# Sheet2.net
KiCad netlist of a schematic drawn in Altium Designer
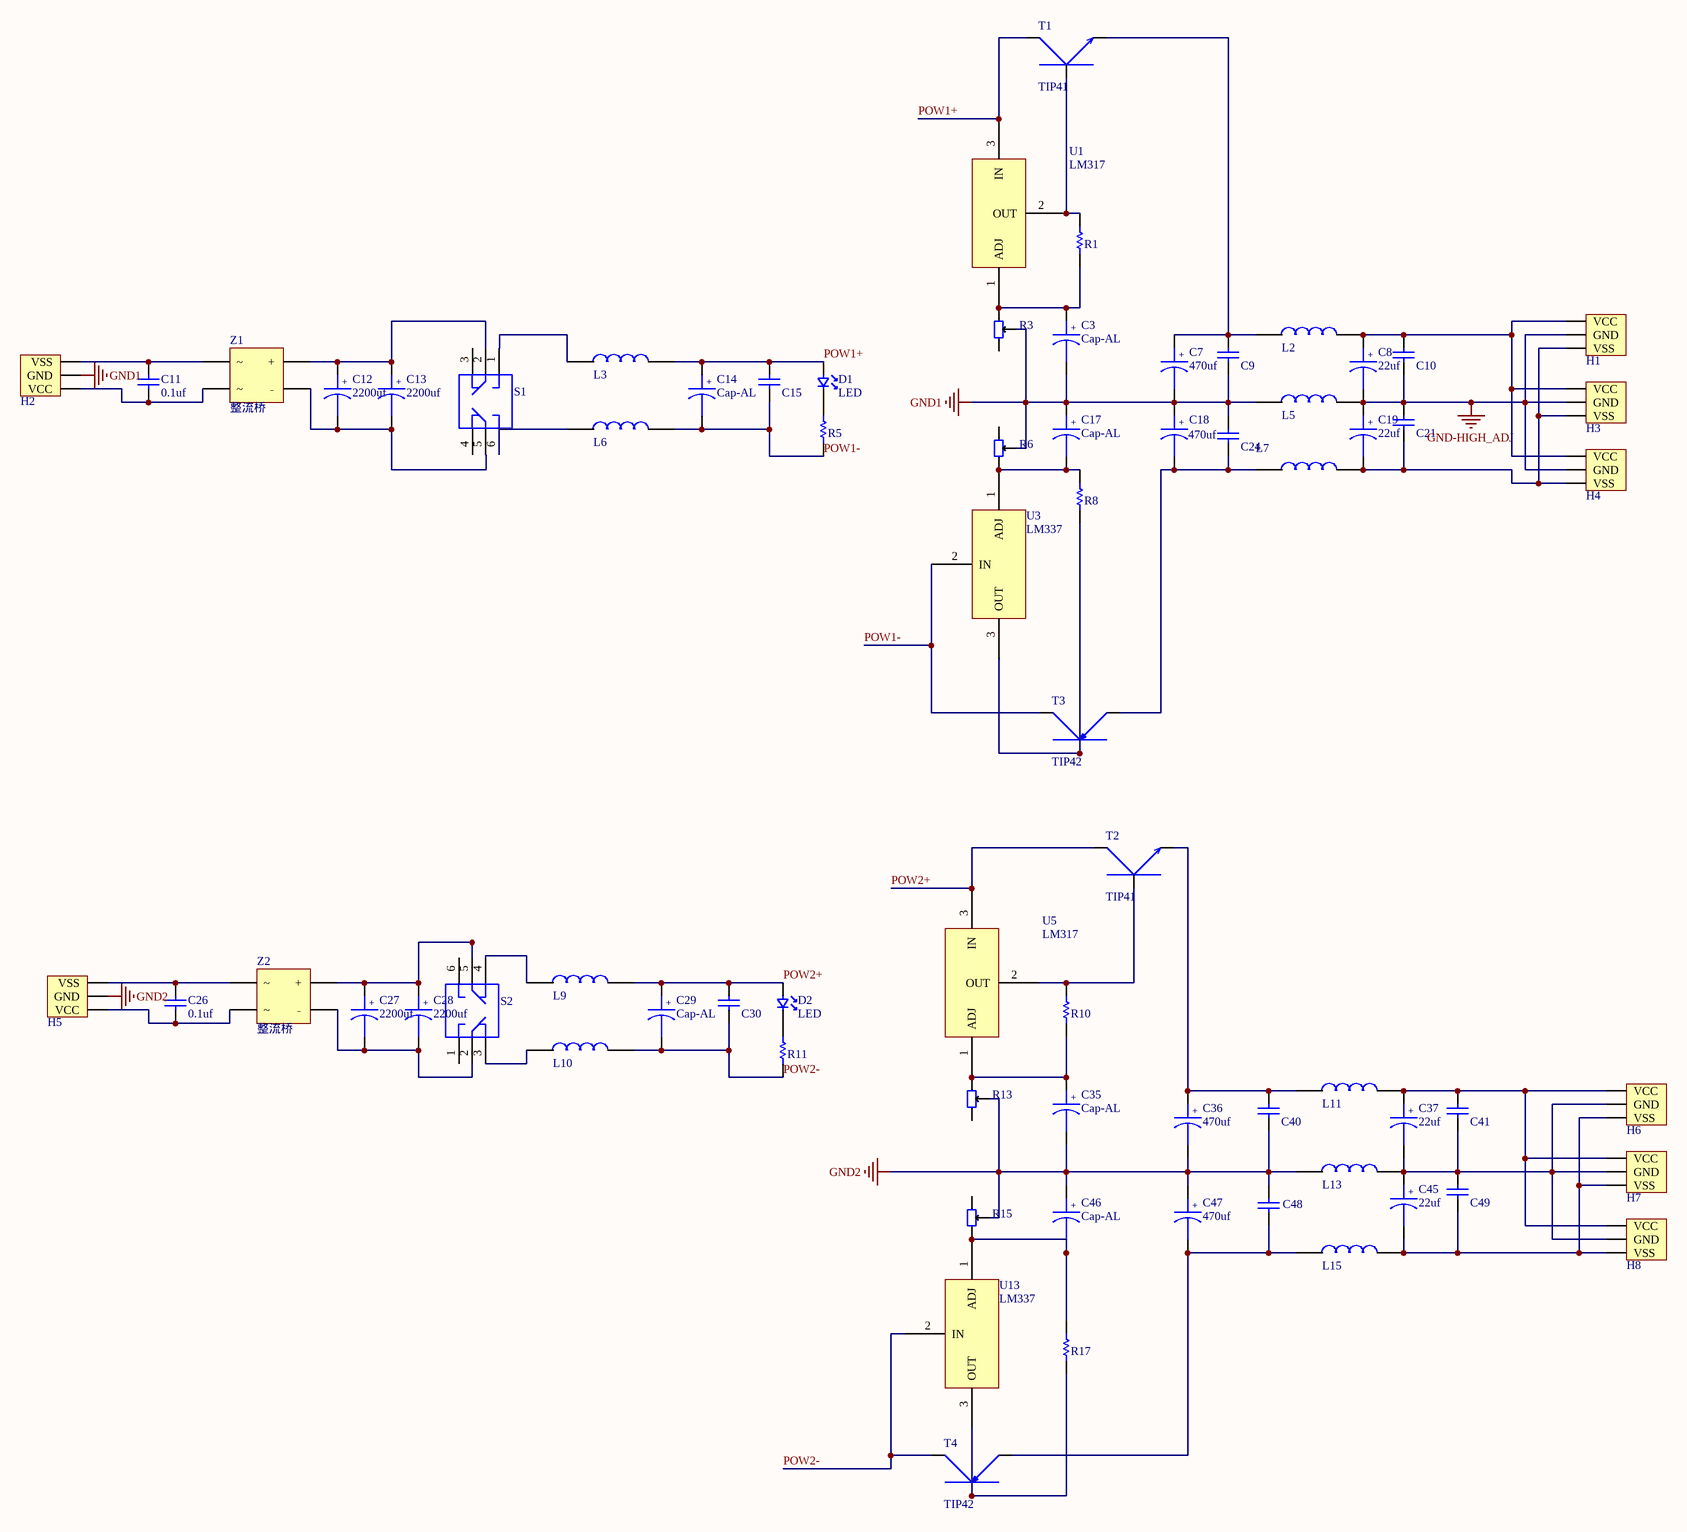
[diagram p0: Sheet2.SchDoc]

(export (version "E")
  (design (tool "Eeschema 10.0.6"))
  (components
    (comp (ref "C3") (value "Cap-AL") (footprint "CD-2.2mm") (libsource (lib "电源") (part "Cap-AL")))
    (comp (ref "C7") (value "470uf") (footprint "CD-5mm") (libsource (lib "电源") (part "Cap-AL")))
    (comp (ref "C8") (value "22uf") (footprint "CD-3mm") (libsource (lib "电源") (part "Cap-AL")))
    (comp (ref "C9") (value "Cap-SEMI") (footprint "独石电容") (libsource (lib "电源") (part "Cap-SEMI")))
    (comp (ref "C10") (value "Cap-SEMI") (footprint "独石电容") (libsource (lib "电源") (part "Cap-SEMI")))
    (comp (ref "C11")
      (value "Cap1")
      (footprint "安规电容")
      (fields (field (name "值") "0.1uf"))
      (libsource (lib "电源") (part "Cap1"))
    )
    (comp (ref "C12") (value "2200uf") (footprint "CD-7.6mm") (libsource (lib "电源") (part "Cap")))
    (comp (ref "C13") (value "2200uf") (footprint "CD-7.6mm") (libsource (lib "电源") (part "Cap")))
    (comp (ref "C14") (value "Cap-AL") (footprint "CD-3mm") (libsource (lib "电源") (part "Cap-AL")))
    (comp (ref "C15") (value "0.1uf") (footprint "独石电容") (libsource (lib "电源") (part "Cap-SEMI")))
    (comp (ref "C17") (value "Cap-AL") (footprint "CD-2.2mm") (libsource (lib "电源") (part "Cap-AL")))
    (comp (ref "C18") (value "470uf") (footprint "CD-5mm") (libsource (lib "电源") (part "Cap-AL")))
    (comp (ref "C19") (value "22uf") (footprint "CD-3mm") (libsource (lib "电源") (part "Cap-AL")))
    (comp (ref "C21") (value "Cap-SEMI") (footprint "独石电容") (libsource (lib "电源") (part "Cap-SEMI")))
    (comp (ref "C24") (value "Cap-SEMI") (footprint "独石电容") (libsource (lib "电源") (part "Cap-SEMI")))
    (comp (ref "C26")
      (value "Cap1")
      (footprint "安规电容")
      (fields (field (name "值") "0.1uf"))
      (libsource (lib "电源") (part "Cap1"))
    )
    (comp (ref "C27") (value "2200uf") (footprint "CD-7.6mm") (libsource (lib "电源") (part "Cap")))
    (comp (ref "C28") (value "2200uf") (footprint "CD-7.6mm") (libsource (lib "电源") (part "Cap")))
    (comp (ref "C29") (value "Cap-AL") (footprint "CD-3mm") (libsource (lib "电源") (part "Cap-AL")))
    (comp (ref "C30") (value "0.1uf") (footprint "独石电容") (libsource (lib "电源") (part "Cap-SEMI")))
    (comp (ref "C35") (value "Cap-AL") (footprint "CD-2.2mm") (libsource (lib "电源") (part "Cap-AL")))
    (comp (ref "C36") (value "470uf") (footprint "CD-5mm") (libsource (lib "电源") (part "Cap-AL")))
    (comp (ref "C37") (value "22uf") (footprint "CD-3mm") (libsource (lib "电源") (part "Cap-AL")))
    (comp (ref "C40") (value "Cap-SEMI") (footprint "独石电容") (libsource (lib "电源") (part "Cap-SEMI")))
    (comp (ref "C41") (value "Cap-SEMI") (footprint "独石电容") (libsource (lib "电源") (part "Cap-SEMI")))
    (comp (ref "C45") (value "22uf") (footprint "CD-3mm") (libsource (lib "电源") (part "Cap-AL")))
    (comp (ref "C46") (value "Cap-AL") (footprint "CD-2.2mm") (libsource (lib "电源") (part "Cap-AL")))
    (comp (ref "C47") (value "470uf") (footprint "CD-5mm") (libsource (lib "电源") (part "Cap-AL")))
    (comp (ref "C48") (value "Cap-SEMI") (footprint "独石电容") (libsource (lib "电源") (part "Cap-SEMI")))
    (comp (ref "C49") (value "Cap-SEMI") (footprint "独石电容") (libsource (lib "电源") (part "Cap-SEMI")))
    (comp (ref "D1") (value "LED") (footprint "0805_s") (libsource (lib "电源") (part "LED")))
    (comp (ref "D2") (value "LED") (footprint "0805_s") (libsource (lib "电源") (part "LED")))
    (comp (ref "H1")
      (value "KF128-5.08-3P")
      (footprint "KF128-5.08-3P")
      (libsource (lib "电源") (part "KF128-5.08-3P"))
    )
    (comp (ref "H2")
      (value "KF128-5.08-3P")
      (footprint "KF128-5.08-3P")
      (libsource (lib "") (part "KF128-5.08-3P_1"))
    )
    (comp (ref "H3")
      (value "KF128-5.08-3P")
      (footprint "KF128-5.08-3P")
      (libsource (lib "电源") (part "KF128-5.08-3P"))
    )
    (comp (ref "H4")
      (value "KF128-5.08-3P")
      (footprint "KF128-5.08-3P")
      (libsource (lib "电源") (part "KF128-5.08-3P"))
    )
    (comp (ref "H5")
      (value "KF128-5.08-3P")
      (footprint "KF128-5.08-3P")
      (libsource (lib "") (part "KF128-5.08-3P_1"))
    )
    (comp (ref "H6")
      (value "KF128-5.08-3P")
      (footprint "KF128-5.08-3P")
      (libsource (lib "电源") (part "KF128-5.08-3P"))
    )
    (comp (ref "H7")
      (value "KF128-5.08-3P")
      (footprint "KF128-5.08-3P")
      (libsource (lib "电源") (part "KF128-5.08-3P"))
    )
    (comp (ref "H8")
      (value "KF128-5.08-3P")
      (footprint "KF128-5.08-3P")
      (libsource (lib "电源") (part "KF128-5.08-3P"))
    )
    (comp (ref "L2") (value "SMD") (footprint "功率电感-12x12 - duplicate") (libsource (lib "电源") (part "功率电感")))
    (comp (ref "L3") (value "SMD") (footprint "功率电感-12x12 - duplicate") (libsource (lib "电源") (part "功率电感")))
    (comp (ref "L5") (value "SMD") (footprint "功率电感-12x12 - duplicate") (libsource (lib "电源") (part "功率电感")))
    (comp (ref "L6") (value "SMD") (footprint "功率电感-12x12 - duplicate") (libsource (lib "电源") (part "功率电感")))
    (comp (ref "L7") (value "SMD") (footprint "功率电感-12x12 - duplicate") (libsource (lib "电源") (part "功率电感")))
    (comp (ref "L9") (value "SMD") (footprint "功率电感-12x12 - duplicate") (libsource (lib "电源") (part "功率电感")))
    (comp (ref "L10") (value "SMD") (footprint "功率电感-12x12 - duplicate") (libsource (lib "电源") (part "功率电感")))
    (comp (ref "L11") (value "SMD") (footprint "功率电感-12x12 - duplicate") (libsource (lib "电源") (part "功率电感")))
    (comp (ref "L13") (value "SMD") (footprint "功率电感-12x12 - duplicate") (libsource (lib "电源") (part "功率电感")))
    (comp (ref "L15") (value "SMD") (footprint "功率电感-12x12 - duplicate") (libsource (lib "电源") (part "功率电感")))
    (comp (ref "R1") (value "RES") (footprint "0805") (libsource (lib "电源") (part "RES")))
    (comp (ref "R3") (value "可调电位器1") (footprint "电位器") (libsource (lib "电源") (part "可调电位器1")))
    (comp (ref "R5") (value "RES") (footprint "0805") (libsource (lib "电源") (part "RES")))
    (comp (ref "R6") (value "可调电位器1") (footprint "电位器") (libsource (lib "电源") (part "可调电位器1")))
    (comp (ref "R8") (value "RES") (footprint "0805") (libsource (lib "电源") (part "RES")))
    (comp (ref "R10") (value "RES") (footprint "0805") (libsource (lib "电源") (part "RES")))
    (comp (ref "R11") (value "RES") (footprint "0805") (libsource (lib "电源") (part "RES")))
    (comp (ref "R13") (value "可调电位器1") (footprint "电位器") (libsource (lib "电源") (part "可调电位器1")))
    (comp (ref "R15") (value "可调电位器1") (footprint "电位器") (libsource (lib "电源") (part "可调电位器1")))
    (comp (ref "R17") (value "RES") (footprint "0805") (libsource (lib "电源") (part "RES")))
    (comp (ref "S1") (value "双掷开关") (footprint "SWITCH") (libsource (lib "电源") (part "双掷开关")))
    (comp (ref "S2") (value "双掷开关") (footprint "SWITCH") (libsource (lib "电源") (part "双掷开关")))
    (comp (ref "T1") (value "TIP41") (footprint "TO-220") (libsource (lib "电源") (part "TIP41")))
    (comp (ref "T2") (value "TIP41") (footprint "TO-220") (libsource (lib "电源") (part "TIP41")))
    (comp (ref "T3") (value "TIP42") (footprint "TO-220") (libsource (lib "电源") (part "TIP42")))
    (comp (ref "T4") (value "TIP42") (footprint "TO-220") (libsource (lib "电源") (part "TIP42")))
    (comp (ref "U1") (value "LM317") (footprint "TO-220") (libsource (lib "电源") (part "LM317")))
    (comp (ref "U3") (value "LM337") (footprint "TO-220") (libsource (lib "电源") (part "LM337")))
    (comp (ref "U5") (value "LM317") (footprint "TO-220") (libsource (lib "电源") (part "LM317")))
    (comp (ref "U13") (value "LM337") (footprint "TO-220") (libsource (lib "电源") (part "LM337")))
    (comp (ref "Z1") (value "整流桥") (footprint "整流桥") (libsource (lib "电源") (part "整流桥")))
    (comp (ref "Z2") (value "整流桥") (footprint "整流桥") (libsource (lib "电源") (part "整流桥")))
  )
  (nets
    (net (code "1") (name "/POW1+") (class "Default")
      (node (ref "C14") (pin "1") (pinfunction "1_1") (pintype "passive"))
      (node (ref "C15") (pin "2") (pinfunction "2_2") (pintype "passive"))
      (node (ref "D1") (pin "2") (pinfunction "2_2") (pintype "passive"))
      (node (ref "L3") (pin "2") (pintype "passive"))
      (node (ref "T1") (pin "2") (pinfunction "2_2") (pintype "passive"))
      (node (ref "U1") (pin "3") (pinfunction "IN_3") (pintype "passive"))
    )
    (net (code "2") (name "/POW1-") (class "Default")
      (node (ref "C14") (pin "2") (pinfunction "2_2") (pintype "passive"))
      (node (ref "C15") (pin "1") (pinfunction "1_1") (pintype "passive"))
      (node (ref "L6") (pin "2") (pintype "passive"))
      (node (ref "R5") (pin "1") (pinfunction "1_1") (pintype "passive"))
      (node (ref "T3") (pin "2") (pinfunction "2_2") (pintype "passive"))
      (node (ref "U3") (pin "2") (pinfunction "IN_2") (pintype "passive"))
    )
    (net (code "3") (name "/POW2+") (class "Default")
      (node (ref "C29") (pin "1") (pinfunction "1_1") (pintype "passive"))
      (node (ref "C30") (pin "2") (pinfunction "2_2") (pintype "passive"))
      (node (ref "D2") (pin "2") (pinfunction "2_2") (pintype "passive"))
      (node (ref "L9") (pin "2") (pintype "passive"))
      (node (ref "T2") (pin "2") (pinfunction "2_2") (pintype "passive"))
      (node (ref "U5") (pin "3") (pinfunction "IN_3") (pintype "passive"))
    )
    (net (code "4") (name "/POW2-") (class "Default")
      (node (ref "C29") (pin "2") (pinfunction "2_2") (pintype "passive"))
      (node (ref "C30") (pin "1") (pinfunction "1_1") (pintype "passive"))
      (node (ref "L10") (pin "2") (pintype "passive"))
      (node (ref "R11") (pin "1") (pinfunction "1_1") (pintype "passive"))
      (node (ref "T4") (pin "2") (pinfunction "2_2") (pintype "passive"))
      (node (ref "U13") (pin "2") (pinfunction "IN_2") (pintype "passive"))
    )
    (net (code "5") (name "GND-HIGH_ADJ") (class "Default")
      (node (ref "C10") (pin "1") (pinfunction "1_1") (pintype "passive"))
      (node (ref "C19") (pin "1") (pinfunction "1_1") (pintype "passive"))
      (node (ref "C21") (pin "2") (pinfunction "2_2") (pintype "passive"))
      (node (ref "C8") (pin "2") (pinfunction "2_2") (pintype "passive"))
      (node (ref "H1") (pin "2") (pinfunction "GND_2") (pintype "passive"))
      (node (ref "H3") (pin "2") (pinfunction "GND_2") (pintype "passive"))
      (node (ref "H4") (pin "2") (pinfunction "GND_2") (pintype "passive"))
      (node (ref "L5") (pin "2") (pintype "passive"))
    )
    (net (code "6") (name "GND1") (class "Default")
      (node (ref "C17") (pin "1") (pinfunction "1_1") (pintype "passive"))
      (node (ref "C18") (pin "1") (pinfunction "1_1") (pintype "passive"))
      (node (ref "C24") (pin "2") (pinfunction "2_2") (pintype "passive"))
      (node (ref "C3") (pin "2") (pinfunction "2_2") (pintype "passive"))
      (node (ref "C7") (pin "2") (pinfunction "2_2") (pintype "passive"))
      (node (ref "C9") (pin "1") (pinfunction "1_1") (pintype "passive"))
      (node (ref "H2") (pin "2") (pinfunction "GND_2") (pintype "passive"))
      (node (ref "L5") (pin "1") (pintype "passive"))
      (node (ref "R3") (pin "2") (pinfunction "2_2") (pintype "passive"))
      (node (ref "R6") (pin "2") (pinfunction "2_2") (pintype "passive"))
    )
    (net (code "7") (name "GND2") (class "Default")
      (node (ref "C35") (pin "2") (pinfunction "2_2") (pintype "passive"))
      (node (ref "C36") (pin "2") (pinfunction "2_2") (pintype "passive"))
      (node (ref "C40") (pin "1") (pinfunction "1_1") (pintype "passive"))
      (node (ref "C46") (pin "1") (pinfunction "1_1") (pintype "passive"))
      (node (ref "C47") (pin "1") (pinfunction "1_1") (pintype "passive"))
      (node (ref "C48") (pin "2") (pinfunction "2_2") (pintype "passive"))
      (node (ref "H5") (pin "2") (pinfunction "GND_2") (pintype "passive"))
      (node (ref "L13") (pin "1") (pintype "passive"))
      (node (ref "R13") (pin "2") (pinfunction "2_2") (pintype "passive"))
      (node (ref "R15") (pin "2") (pinfunction "2_2") (pintype "passive"))
    )
    (net (code "8") (name "Net-(C7-Pad1)") (class "Default")
      (node (ref "C7") (pin "1") (pinfunction "1_1") (pintype "passive"))
      (node (ref "C9") (pin "2") (pinfunction "2_2") (pintype "passive"))
      (node (ref "L2") (pin "1") (pintype "passive"))
      (node (ref "T1") (pin "3") (pinfunction "3_3") (pintype "passive"))
    )
    (net (code "9") (name "Net-(C18-Pad2)") (class "Default")
      (node (ref "C18") (pin "2") (pinfunction "2_2") (pintype "passive"))
      (node (ref "C24") (pin "1") (pinfunction "1_1") (pintype "passive"))
      (node (ref "L7") (pin "1") (pintype "passive"))
      (node (ref "T3") (pin "3") (pinfunction "3_3") (pintype "passive"))
    )
    (net (code "10") (name "Net-(C36-Pad1)") (class "Default")
      (node (ref "C36") (pin "1") (pinfunction "1_1") (pintype "passive"))
      (node (ref "C40") (pin "2") (pinfunction "2_2") (pintype "passive"))
      (node (ref "L11") (pin "1") (pintype "passive"))
      (node (ref "T2") (pin "3") (pinfunction "3_3") (pintype "passive"))
    )
    (net (code "11") (name "Net-(C47-Pad2)") (class "Default")
      (node (ref "C47") (pin "2") (pinfunction "2_2") (pintype "passive"))
      (node (ref "C48") (pin "1") (pinfunction "1_1") (pintype "passive"))
      (node (ref "L15") (pin "1") (pintype "passive"))
      (node (ref "T4") (pin "3") (pinfunction "3_3") (pintype "passive"))
    )
    (net (code "12") (name "Net-(D1-Pad1)") (class "Default")
      (node (ref "D1") (pin "1") (pinfunction "1_1") (pintype "passive"))
      (node (ref "R5") (pin "2") (pinfunction "2_2") (pintype "passive"))
    )
    (net (code "13") (name "Net-(D2-Pad1)") (class "Default")
      (node (ref "D2") (pin "1") (pinfunction "1_1") (pintype "passive"))
      (node (ref "R11") (pin "2") (pinfunction "2_2") (pintype "passive"))
    )
    (net (code "14") (name "Net-(H1-VCC)") (class "Default")
      (node (ref "C10") (pin "2") (pinfunction "2_2") (pintype "passive"))
      (node (ref "C8") (pin "1") (pinfunction "1_1") (pintype "passive"))
      (node (ref "H1") (pin "1") (pinfunction "VCC_1") (pintype "passive"))
      (node (ref "H3") (pin "1") (pinfunction "VCC_1") (pintype "passive"))
      (node (ref "H4") (pin "1") (pinfunction "VCC_1") (pintype "passive"))
      (node (ref "L2") (pin "2") (pintype "passive"))
    )
    (net (code "15") (name "Net-(H1-VSS)") (class "Default")
      (node (ref "C19") (pin "2") (pinfunction "2_2") (pintype "passive"))
      (node (ref "C21") (pin "1") (pinfunction "1_1") (pintype "passive"))
      (node (ref "H1") (pin "3") (pinfunction "VSS_3") (pintype "passive"))
      (node (ref "H3") (pin "3") (pinfunction "VSS_3") (pintype "passive"))
      (node (ref "H4") (pin "3") (pinfunction "VSS_3") (pintype "passive"))
      (node (ref "L7") (pin "2") (pintype "passive"))
    )
    (net (code "16") (name "Net-(H2-VCC)") (class "Default")
      (node (ref "C11") (pin "1") (pinfunction "1_1") (pintype "passive"))
      (node (ref "H2") (pin "1") (pinfunction "VCC_1") (pintype "passive"))
      (node (ref "Z1") (pin "3") (pinfunction "~_3") (pintype "passive"))
    )
    (net (code "17") (name "Net-(H2-VSS)") (class "Default")
      (node (ref "C11") (pin "2") (pinfunction "2_2") (pintype "passive"))
      (node (ref "H2") (pin "3") (pinfunction "VSS_3") (pintype "passive"))
      (node (ref "Z1") (pin "2") (pinfunction "~_2") (pintype "passive"))
    )
    (net (code "18") (name "Net-(H5-VCC)") (class "Default")
      (node (ref "C26") (pin "1") (pinfunction "1_1") (pintype "passive"))
      (node (ref "H5") (pin "1") (pinfunction "VCC_1") (pintype "passive"))
      (node (ref "Z2") (pin "3") (pinfunction "~_3") (pintype "passive"))
    )
    (net (code "19") (name "Net-(H5-VSS)") (class "Default")
      (node (ref "C26") (pin "2") (pinfunction "2_2") (pintype "passive"))
      (node (ref "H5") (pin "3") (pinfunction "VSS_3") (pintype "passive"))
      (node (ref "Z2") (pin "2") (pinfunction "~_2") (pintype "passive"))
    )
    (net (code "20") (name "Net-(H6-GND)") (class "Default")
      (node (ref "C37") (pin "2") (pinfunction "2_2") (pintype "passive"))
      (node (ref "C41") (pin "1") (pinfunction "1_1") (pintype "passive"))
      (node (ref "C45") (pin "1") (pinfunction "1_1") (pintype "passive"))
      (node (ref "C49") (pin "2") (pinfunction "2_2") (pintype "passive"))
      (node (ref "H6") (pin "2") (pinfunction "GND_2") (pintype "passive"))
      (node (ref "H7") (pin "2") (pinfunction "GND_2") (pintype "passive"))
      (node (ref "H8") (pin "2") (pinfunction "GND_2") (pintype "passive"))
      (node (ref "L13") (pin "2") (pintype "passive"))
    )
    (net (code "21") (name "Net-(H6-VCC)") (class "Default")
      (node (ref "C37") (pin "1") (pinfunction "1_1") (pintype "passive"))
      (node (ref "C41") (pin "2") (pinfunction "2_2") (pintype "passive"))
      (node (ref "H6") (pin "1") (pinfunction "VCC_1") (pintype "passive"))
      (node (ref "H7") (pin "1") (pinfunction "VCC_1") (pintype "passive"))
      (node (ref "H8") (pin "1") (pinfunction "VCC_1") (pintype "passive"))
      (node (ref "L11") (pin "2") (pintype "passive"))
    )
    (net (code "22") (name "Net-(H6-VSS)") (class "Default")
      (node (ref "C45") (pin "2") (pinfunction "2_2") (pintype "passive"))
      (node (ref "C49") (pin "1") (pinfunction "1_1") (pintype "passive"))
      (node (ref "H6") (pin "3") (pinfunction "VSS_3") (pintype "passive"))
      (node (ref "H7") (pin "3") (pinfunction "VSS_3") (pintype "passive"))
      (node (ref "H8") (pin "3") (pinfunction "VSS_3") (pintype "passive"))
      (node (ref "L15") (pin "2") (pintype "passive"))
    )
    (net (code "23") (name "Net-(L3-Pad1)") (class "Default")
      (node (ref "L3") (pin "1") (pintype "passive"))
      (node (ref "S1") (pin "1") (pinfunction "1_1") (pintype "passive"))
    )
    (net (code "24") (name "Net-(L6-Pad1)") (class "Default")
      (node (ref "L6") (pin "1") (pintype "passive"))
      (node (ref "S1") (pin "6") (pinfunction "6_6") (pintype "passive"))
    )
    (net (code "25") (name "Net-(L9-Pad1)") (class "Default")
      (node (ref "L9") (pin "1") (pintype "passive"))
      (node (ref "S2") (pin "4") (pinfunction "4_4") (pintype "passive"))
    )
    (net (code "26") (name "Net-(L10-Pad1)") (class "Default")
      (node (ref "L10") (pin "1") (pintype "passive"))
      (node (ref "S2") (pin "3") (pinfunction "3_3") (pintype "passive"))
    )
    (net (code "27") (name "Net-(U1-ADJ)") (class "Default")
      (node (ref "C3") (pin "1") (pinfunction "1_1") (pintype "passive"))
      (node (ref "R1") (pin "1") (pinfunction "1_1") (pintype "passive"))
      (node (ref "R3") (pin "3") (pinfunction "3_3") (pintype "passive"))
      (node (ref "U1") (pin "1") (pinfunction "ADJ_1") (pintype "passive"))
    )
    (net (code "28") (name "Net-(U1-OUT)") (class "Default")
      (node (ref "R1") (pin "2") (pinfunction "2_2") (pintype "passive"))
      (node (ref "T1") (pin "1") (pinfunction "1_1") (pintype "passive"))
      (node (ref "U1") (pin "2") (pinfunction "OUT_2") (pintype "passive"))
    )
    (net (code "29") (name "Net-(U3-ADJ)") (class "Default")
      (node (ref "C17") (pin "2") (pinfunction "2_2") (pintype "passive"))
      (node (ref "R6") (pin "1") (pinfunction "1_1") (pintype "passive"))
      (node (ref "R8") (pin "2") (pinfunction "2_2") (pintype "passive"))
      (node (ref "U3") (pin "1") (pinfunction "ADJ_1") (pintype "passive"))
    )
    (net (code "30") (name "Net-(U3-OUT)") (class "Default")
      (node (ref "R8") (pin "1") (pinfunction "1_1") (pintype "passive"))
      (node (ref "T3") (pin "1") (pinfunction "1_1") (pintype "passive"))
      (node (ref "U3") (pin "3") (pinfunction "OUT_3") (pintype "passive"))
    )
    (net (code "31") (name "Net-(U5-ADJ)") (class "Default")
      (node (ref "C35") (pin "1") (pinfunction "1_1") (pintype "passive"))
      (node (ref "R10") (pin "1") (pinfunction "1_1") (pintype "passive"))
      (node (ref "R13") (pin "3") (pinfunction "3_3") (pintype "passive"))
      (node (ref "U5") (pin "1") (pinfunction "ADJ_1") (pintype "passive"))
    )
    (net (code "32") (name "Net-(U5-OUT)") (class "Default")
      (node (ref "R10") (pin "2") (pinfunction "2_2") (pintype "passive"))
      (node (ref "T2") (pin "1") (pinfunction "1_1") (pintype "passive"))
      (node (ref "U5") (pin "2") (pinfunction "OUT_2") (pintype "passive"))
    )
    (net (code "33") (name "Net-(U13-ADJ)") (class "Default")
      (node (ref "C46") (pin "2") (pinfunction "2_2") (pintype "passive"))
      (node (ref "R15") (pin "1") (pinfunction "1_1") (pintype "passive"))
      (node (ref "R17") (pin "2") (pinfunction "2_2") (pintype "passive"))
      (node (ref "U13") (pin "1") (pinfunction "ADJ_1") (pintype "passive"))
    )
    (net (code "34") (name "Net-(U13-OUT)") (class "Default")
      (node (ref "R17") (pin "1") (pinfunction "1_1") (pintype "passive"))
      (node (ref "T4") (pin "1") (pinfunction "1_1") (pintype "passive"))
      (node (ref "U13") (pin "3") (pinfunction "OUT_3") (pintype "passive"))
    )
    (net (code "35") (name "Net-(Z1-+)") (class "Default")
      (node (ref "C12") (pin "1") (pinfunction "1_1") (pintype "passive"))
      (node (ref "C13") (pin "1") (pinfunction "1_1") (pintype "passive"))
      (node (ref "S1") (pin "2") (pinfunction "2_2") (pintype "passive"))
      (node (ref "Z1") (pin "1") (pinfunction "+_1") (pintype "passive"))
    )
    (net (code "36") (name "Net-(Z1-﹣)") (class "Default")
      (node (ref "C12") (pin "2") (pinfunction "2_2") (pintype "passive"))
      (node (ref "C13") (pin "2") (pinfunction "2_2") (pintype "passive"))
      (node (ref "S1") (pin "5") (pinfunction "5_5") (pintype "passive"))
      (node (ref "Z1") (pin "4") (pinfunction "﹣_4") (pintype "passive"))
    )
    (net (code "37") (name "Net-(Z2-+)") (class "Default")
      (node (ref "C27") (pin "1") (pinfunction "1_1") (pintype "passive"))
      (node (ref "C28") (pin "1") (pinfunction "1_1") (pintype "passive"))
      (node (ref "S2") (pin "5") (pinfunction "5_5") (pintype "passive"))
      (node (ref "Z2") (pin "1") (pinfunction "+_1") (pintype "passive"))
    )
    (net (code "38") (name "Net-(Z2-﹣)") (class "Default")
      (node (ref "C27") (pin "2") (pinfunction "2_2") (pintype "passive"))
      (node (ref "C28") (pin "2") (pinfunction "2_2") (pintype "passive"))
      (node (ref "S2") (pin "2") (pinfunction "2_2") (pintype "passive"))
      (node (ref "Z2") (pin "4") (pinfunction "﹣_4") (pintype "passive"))
    )
    (net (code "39") (name "unconnected-(R3-Pad1)") (class "Default")
      (node (ref "R3") (pin "1") (pinfunction "1_1") (pintype "passive"))
    )
    (net (code "40") (name "unconnected-(R6-Pad3)") (class "Default")
      (node (ref "R6") (pin "3") (pinfunction "3_3") (pintype "passive"))
    )
    (net (code "41") (name "unconnected-(R13-Pad1)") (class "Default")
      (node (ref "R13") (pin "1") (pinfunction "1_1") (pintype "passive"))
    )
    (net (code "42") (name "unconnected-(R15-Pad3)") (class "Default")
      (node (ref "R15") (pin "3") (pinfunction "3_3") (pintype "passive"))
    )
    (net (code "43") (name "unconnected-(S1-Pad3)") (class "Default")
      (node (ref "S1") (pin "3") (pinfunction "3_3") (pintype "passive"))
    )
    (net (code "44") (name "unconnected-(S1-Pad4)") (class "Default")
      (node (ref "S1") (pin "4") (pinfunction "4_4") (pintype "passive"))
    )
    (net (code "45") (name "unconnected-(S2-Pad1)") (class "Default")
      (node (ref "S2") (pin "1") (pinfunction "1_1") (pintype "passive"))
    )
    (net (code "46") (name "unconnected-(S2-Pad6)") (class "Default")
      (node (ref "S2") (pin "6") (pinfunction "6_6") (pintype "passive"))
    )
  )
)
